# SolarPanels_Power_Processing.net
KiCad netlist of a schematic drawn in EAGLE
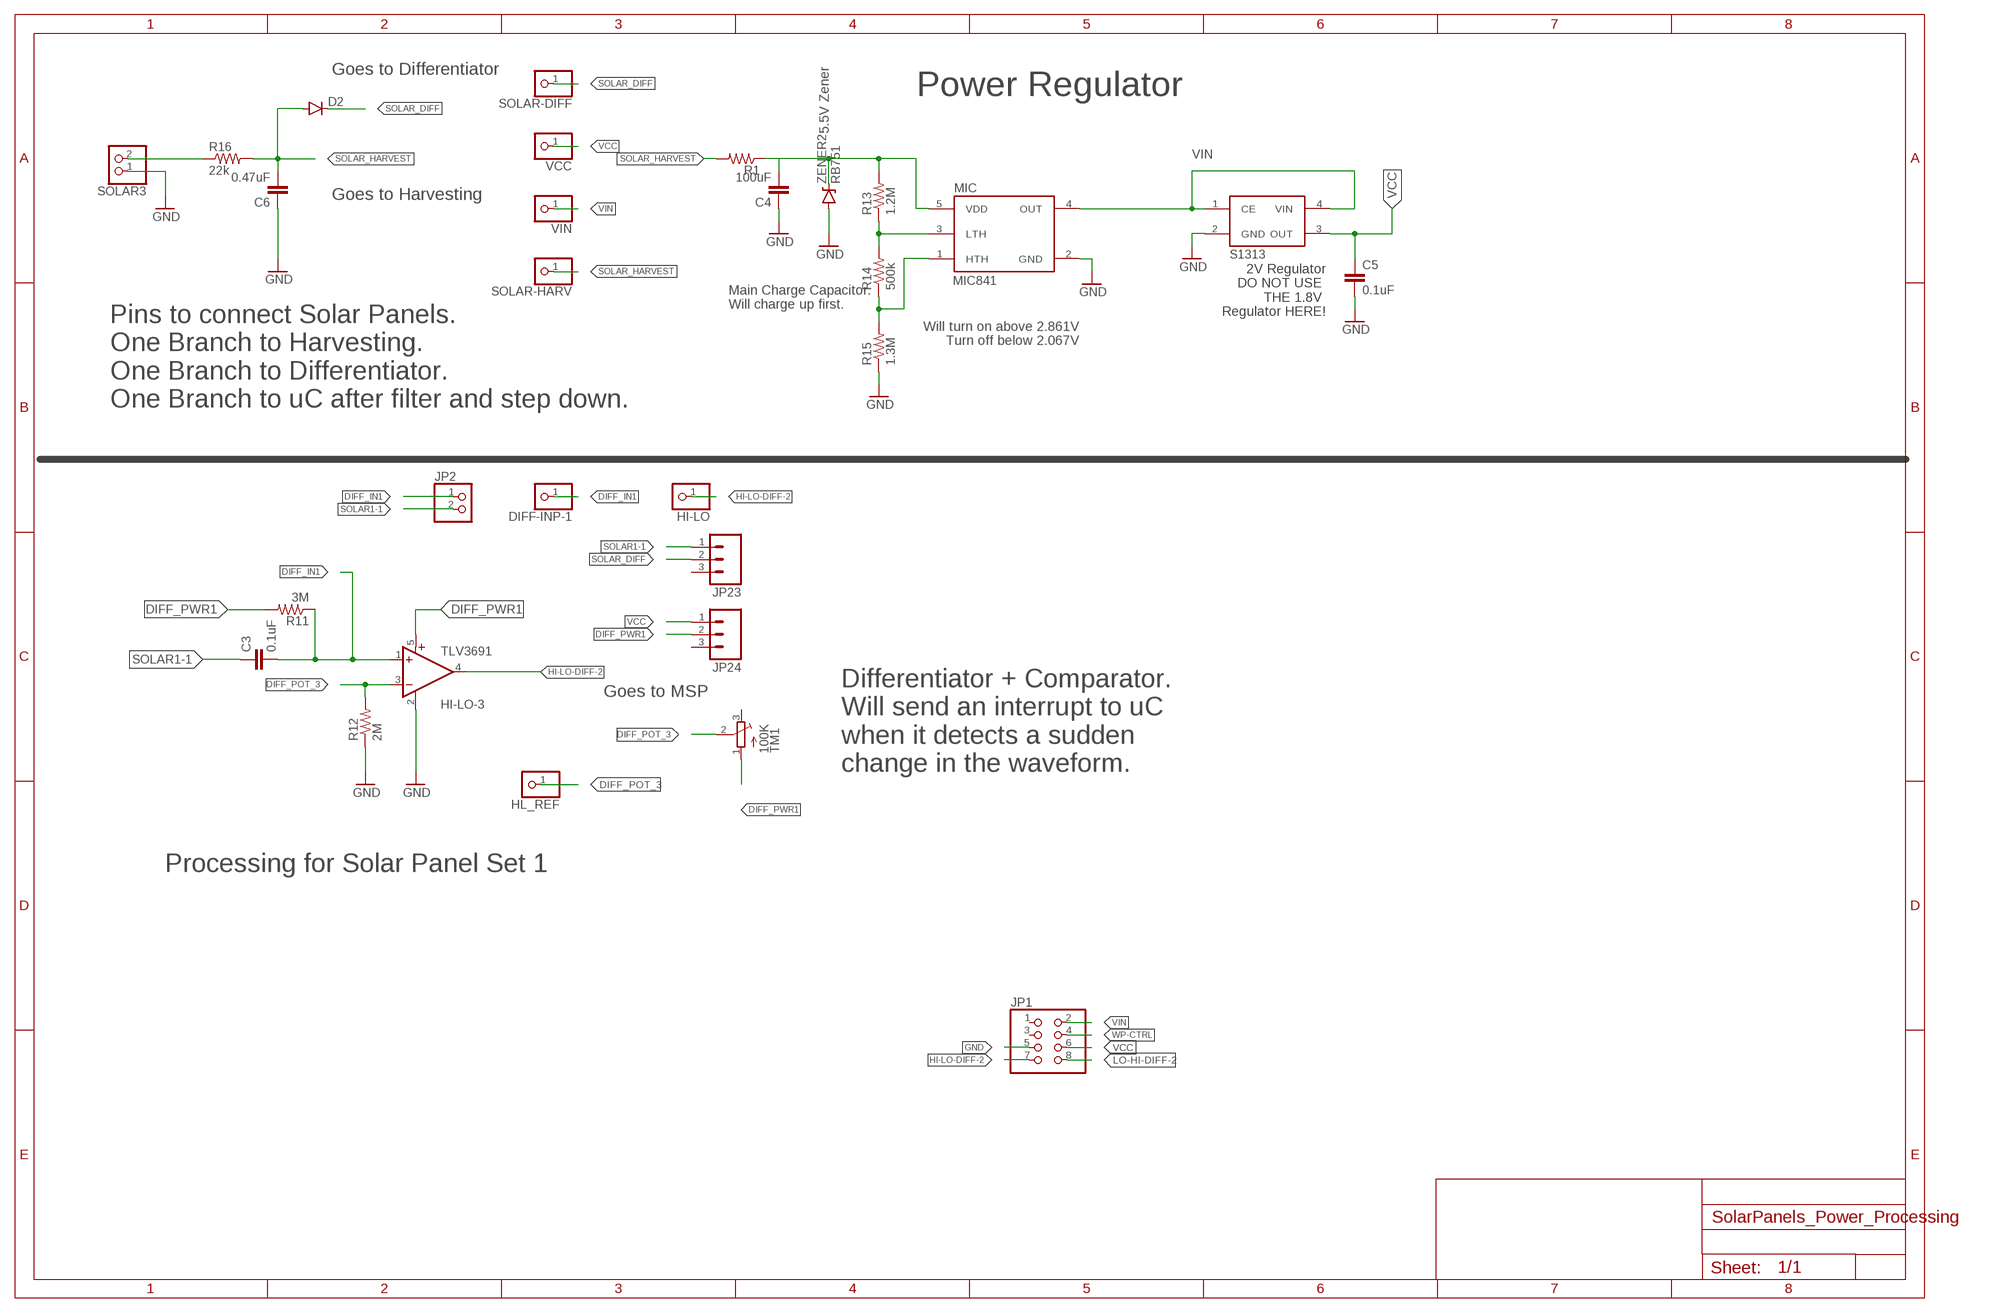
[diagram p0: schematic, sheet 1]

(export (version "E")
  (design (tool "Eeschema 10.0.6"))
  (components
    (comp (ref "C3")
      (value "0.1uF")
      (footprint "eagle-import:0805")
      (libsource (lib "eagle-import") (part "CAP0805"))
    )
    (comp (ref "C4")
      (value "100uF")
      (footprint "eagle-import:0805")
      (libsource (lib "eagle-import") (part "CAP0805"))
    )
    (comp (ref "C5")
      (value "0.1uF")
      (footprint "eagle-import:0805")
      (libsource (lib "eagle-import") (part "CAP0805"))
    )
    (comp (ref "C6")
      (value "0.47uF")
      (footprint "eagle-import:0805")
      (libsource (lib "eagle-import") (part "CAP0805"))
    )
    (comp (ref "D2")
      (value "DIODESOD523")
      (footprint "eagle-import:SOD523")
      (libsource (lib "eagle-import") (part "DIODESOD523"))
    )
    (comp (ref "DIFF-INP-1")
      (value "PINHD-1X1")
      (footprint "eagle-import:1X01")
      (libsource (lib "eagle-import") (part "PINHD-1X1"))
    )
    (comp (ref "HI-LO")
      (value "PINHD-1X1")
      (footprint "eagle-import:1X01")
      (libsource (lib "eagle-import") (part "PINHD-1X1"))
    )
    (comp (ref "HI-LO-3")
      (value "TLV3691")
      (footprint "eagle-import:SC70-5")
      (libsource (lib "eagle-import") (part "TLV3691"))
    )
    (comp (ref "HL_REF")
      (value "PINHD-1X1")
      (footprint "eagle-import:1X01")
      (libsource (lib "eagle-import") (part "PINHD-1X1"))
    )
    (comp (ref "JP1")
      (value "PINHD-2X4/90")
      (footprint "eagle-import:2X04_90")
      (libsource (lib "eagle-import") (part "PINHD-2X4/90"))
    )
    (comp (ref "JP2")
      (value "PINHD-1X2")
      (footprint "eagle-import:1X02")
      (libsource (lib "eagle-import") (part "pinhead_325_PINHD-1X2"))
    )
    (comp (ref "JP23")
      (value "M03")
      (footprint "eagle-import:1X03-1.27MM")
      (libsource (lib "eagle-import") (part "M03"))
    )
    (comp (ref "JP24")
      (value "M03")
      (footprint "eagle-import:1X03-1.27MM")
      (libsource (lib "eagle-import") (part "M03"))
    )
    (comp (ref "MIC")
      (value "MIC841")
      (footprint "eagle-import:SC70-5")
      (libsource (lib "eagle-import") (part "MIC841"))
    )
    (comp (ref "NCP")
      (value "S1313")
      (footprint "eagle-import:SC82-AB_1PRIMARY")
      (libsource (lib "eagle-import") (part "NCP583"))
    )
    (comp (ref "R1")
      (value "RESISTOR0805-RES")
      (footprint "eagle-import:0805")
      (libsource (lib "eagle-import") (part "RESISTOR0805-RES"))
    )
    (comp (ref "R11")
      (value "3M")
      (footprint "eagle-import:0805")
      (libsource (lib "eagle-import") (part "RESISTOR0805-RES"))
    )
    (comp (ref "R12")
      (value "2M")
      (footprint "eagle-import:0805")
      (libsource (lib "eagle-import") (part "RESISTOR0805-RES"))
    )
    (comp (ref "R13")
      (value "1.2M")
      (footprint "eagle-import:0805")
      (libsource (lib "eagle-import") (part "RESISTOR0805-RES"))
    )
    (comp (ref "R14")
      (value "500k")
      (footprint "eagle-import:0805")
      (libsource (lib "eagle-import") (part "RESISTOR0805-RES"))
    )
    (comp (ref "R15")
      (value "1.3M")
      (footprint "eagle-import:0805")
      (libsource (lib "eagle-import") (part "RESISTOR0805-RES"))
    )
    (comp (ref "R16")
      (value "22k")
      (footprint "eagle-import:0805")
      (libsource (lib "eagle-import") (part "RESISTOR0805-RES"))
    )
    (comp (ref "SOLAR-DIFF")
      (value "PINHD-1X1")
      (footprint "eagle-import:1X01")
      (libsource (lib "eagle-import") (part "PINHD-1X1"))
    )
    (comp (ref "SOLAR-HARV")
      (value "PINHD-1X1")
      (footprint "eagle-import:1X01")
      (libsource (lib "eagle-import") (part "PINHD-1X1"))
    )
    (comp (ref "SOLAR3")
      (value "PINHD-1X2")
      (footprint "eagle-import:1X02")
      (libsource (lib "eagle-import") (part "PINHD-1X2"))
    )
    (comp (ref "TM1")
      (value "100K")
      (footprint "eagle-import:TC33X")
      (libsource (lib "eagle-import") (part "TRIMPOTTC33X"))
    )
    (comp (ref "VCC")
      (value "PINHD-1X1")
      (footprint "eagle-import:1X01")
      (libsource (lib "eagle-import") (part "PINHD-1X1"))
    )
    (comp (ref "VIN")
      (value "PINHD-1X1")
      (footprint "eagle-import:1X01")
      (libsource (lib "eagle-import") (part "PINHD-1X1"))
    )
    (comp (ref "ZENER2")
      (value "RB751")
      (footprint "eagle-import:SOD-523")
      (libsource (lib "eagle-import") (part "DIODE-ZENER"))
    )
  )
  (nets
    (net (code "1") (name "DIFF_IN1") (class "Default")
      (node (ref "C3") (pin "2") (pinfunction "2_2") (pintype "passive"))
      (node (ref "DIFF-INP-1") (pin "1") (pinfunction "1_1") (pintype "passive"))
      (node (ref "HI-LO-3") (pin "1") (pinfunction "+IN_1") (pintype "input"))
      (node (ref "JP2") (pin "1") (pinfunction "1_1") (pintype "passive"))
      (node (ref "R11") (pin "1") (pinfunction "1_1") (pintype "passive"))
    )
    (net (code "2") (name "DIFF_POT_3") (class "Default")
      (node (ref "HI-LO-3") (pin "3") (pinfunction "-IN_3") (pintype "input"))
      (node (ref "HL_REF") (pin "1") (pinfunction "1_1") (pintype "passive"))
      (node (ref "R12") (pin "2") (pinfunction "2_2") (pintype "passive"))
      (node (ref "TM1") (pin "2") (pinfunction "S_2") (pintype "passive"))
    )
    (net (code "3") (name "DIFF_PWR1") (class "Default")
      (node (ref "HI-LO-3") (pin "5") (pinfunction "V+_5") (pintype "power_in"))
      (node (ref "JP24") (pin "2") (pinfunction "2_2") (pintype "passive"))
      (node (ref "R11") (pin "2") (pinfunction "2_2") (pintype "passive"))
      (node (ref "TM1") (pin "1") (pinfunction "A_1") (pintype "passive"))
    )
    (net (code "4") (name "GND") (class "Default")
      (node (ref "C4") (pin "1") (pinfunction "1_1") (pintype "passive"))
      (node (ref "C5") (pin "2") (pinfunction "2_2") (pintype "passive"))
      (node (ref "C6") (pin "1") (pinfunction "1_1") (pintype "passive"))
      (node (ref "HI-LO-3") (pin "2") (pinfunction "GND_2") (pintype "power_in"))
      (node (ref "JP1") (pin "5") (pinfunction "5_5") (pintype "passive"))
      (node (ref "MIC") (pin "2") (pinfunction "GND_2") (pintype "bidirectional"))
      (node (ref "NCP") (pin "2") (pinfunction "GND_2") (pintype "bidirectional"))
      (node (ref "R12") (pin "1") (pinfunction "1_1") (pintype "passive"))
      (node (ref "R15") (pin "1") (pinfunction "1_1") (pintype "passive"))
      (node (ref "SOLAR3") (pin "1") (pinfunction "1_1") (pintype "passive"))
      (node (ref "ZENER2") (pin "ANODE") (pinfunction "A_ANODE") (pintype "passive"))
    )
    (net (code "5") (name "HI-LO-DIFF-2") (class "Default")
      (node (ref "HI-LO") (pin "1") (pinfunction "1_1") (pintype "passive"))
      (node (ref "HI-LO-3") (pin "4") (pinfunction "OUT_4") (pintype "output"))
      (node (ref "JP1") (pin "7") (pinfunction "7_7") (pintype "passive"))
    )
    (net (code "6") (name "LO-HI-DIFF-2") (class "Default")
      (node (ref "JP1") (pin "8") (pinfunction "8_8") (pintype "passive"))
    )
    (net (code "7") (name "Net-(MIC-HTH)") (class "Default")
      (node (ref "MIC") (pin "1") (pinfunction "HTH_1") (pintype "bidirectional"))
      (node (ref "R14") (pin "1") (pinfunction "1_1") (pintype "passive"))
      (node (ref "R15") (pin "2") (pinfunction "2_2") (pintype "passive"))
    )
    (net (code "8") (name "Net-(MIC-LTH)") (class "Default")
      (node (ref "MIC") (pin "3") (pinfunction "LTH_3") (pintype "bidirectional"))
      (node (ref "R13") (pin "1") (pinfunction "1_1") (pintype "passive"))
      (node (ref "R14") (pin "2") (pinfunction "2_2") (pintype "passive"))
    )
    (net (code "9") (name "Net-(MIC-VDD)") (class "Default")
      (node (ref "C4") (pin "2") (pinfunction "2_2") (pintype "passive"))
      (node (ref "MIC") (pin "5") (pinfunction "VDD_5") (pintype "bidirectional"))
      (node (ref "R1") (pin "1") (pinfunction "1_1") (pintype "passive"))
      (node (ref "R13") (pin "2") (pinfunction "2_2") (pintype "passive"))
      (node (ref "ZENER2") (pin "CATHODE") (pinfunction "C_CATHODE") (pintype "passive"))
    )
    (net (code "10") (name "Net-(R16-Pad1)") (class "Default")
      (node (ref "R16") (pin "1") (pinfunction "1_1") (pintype "passive"))
      (node (ref "SOLAR3") (pin "2") (pinfunction "2_2") (pintype "passive"))
    )
    (net (code "11") (name "SOLAR1-1") (class "Default")
      (node (ref "C3") (pin "1") (pinfunction "1_1") (pintype "passive"))
      (node (ref "JP2") (pin "2") (pinfunction "2_2") (pintype "passive"))
      (node (ref "JP23") (pin "1") (pinfunction "1_1") (pintype "passive"))
    )
    (net (code "12") (name "SOLAR_DIFF") (class "Default")
      (node (ref "D2") (pin "C") (pinfunction "C_C") (pintype "passive"))
      (node (ref "JP23") (pin "2") (pinfunction "2_2") (pintype "passive"))
      (node (ref "SOLAR-DIFF") (pin "1") (pinfunction "1_1") (pintype "passive"))
    )
    (net (code "13") (name "SOLAR_HARVEST") (class "Default")
      (node (ref "C6") (pin "2") (pinfunction "2_2") (pintype "passive"))
      (node (ref "D2") (pin "A") (pinfunction "A_A") (pintype "passive"))
      (node (ref "R1") (pin "2") (pinfunction "2_2") (pintype "passive"))
      (node (ref "R16") (pin "2") (pinfunction "2_2") (pintype "passive"))
      (node (ref "SOLAR-HARV") (pin "1") (pinfunction "1_1") (pintype "passive"))
    )
    (net (code "14") (name "VCC") (class "Default")
      (node (ref "C5") (pin "1") (pinfunction "1_1") (pintype "passive"))
      (node (ref "JP1") (pin "6") (pinfunction "6_6") (pintype "passive"))
      (node (ref "JP24") (pin "1") (pinfunction "1_1") (pintype "passive"))
      (node (ref "NCP") (pin "3") (pinfunction "OUT_3") (pintype "bidirectional"))
      (node (ref "VCC") (pin "1") (pinfunction "1_1") (pintype "passive"))
    )
    (net (code "15") (name "VIN") (class "Default")
      (node (ref "JP1") (pin "2") (pinfunction "2_2") (pintype "passive"))
      (node (ref "MIC") (pin "4") (pinfunction "OUT_4") (pintype "bidirectional"))
      (node (ref "NCP") (pin "1") (pinfunction "CE_1") (pintype "bidirectional"))
      (node (ref "NCP") (pin "4") (pinfunction "VIN_4") (pintype "bidirectional"))
      (node (ref "VIN") (pin "1") (pinfunction "1_1") (pintype "passive"))
    )
    (net (code "16") (name "WP-CTRL") (class "Default")
      (node (ref "JP1") (pin "4") (pinfunction "4_4") (pintype "passive"))
    )
    (net (code "17") (name "unconnected-(JP1-Pad1)") (class "Default")
      (node (ref "JP1") (pin "1") (pinfunction "1_1") (pintype "passive"))
    )
    (net (code "18") (name "unconnected-(JP1-Pad3)") (class "Default")
      (node (ref "JP1") (pin "3") (pinfunction "3_3") (pintype "passive"))
    )
    (net (code "19") (name "unconnected-(JP23-Pad3)") (class "Default")
      (node (ref "JP23") (pin "3") (pinfunction "3_3") (pintype "passive"))
    )
    (net (code "20") (name "unconnected-(JP24-Pad3)") (class "Default")
      (node (ref "JP24") (pin "3") (pinfunction "3_3") (pintype "passive"))
    )
    (net (code "21") (name "unconnected-(TM1-E-Pad3)") (class "Default")
      (node (ref "TM1") (pin "3") (pinfunction "E_3") (pintype "passive"))
    )
  )
)
